# JP-LED.net
KiCad netlist of a schematic drawn in Altium Designer
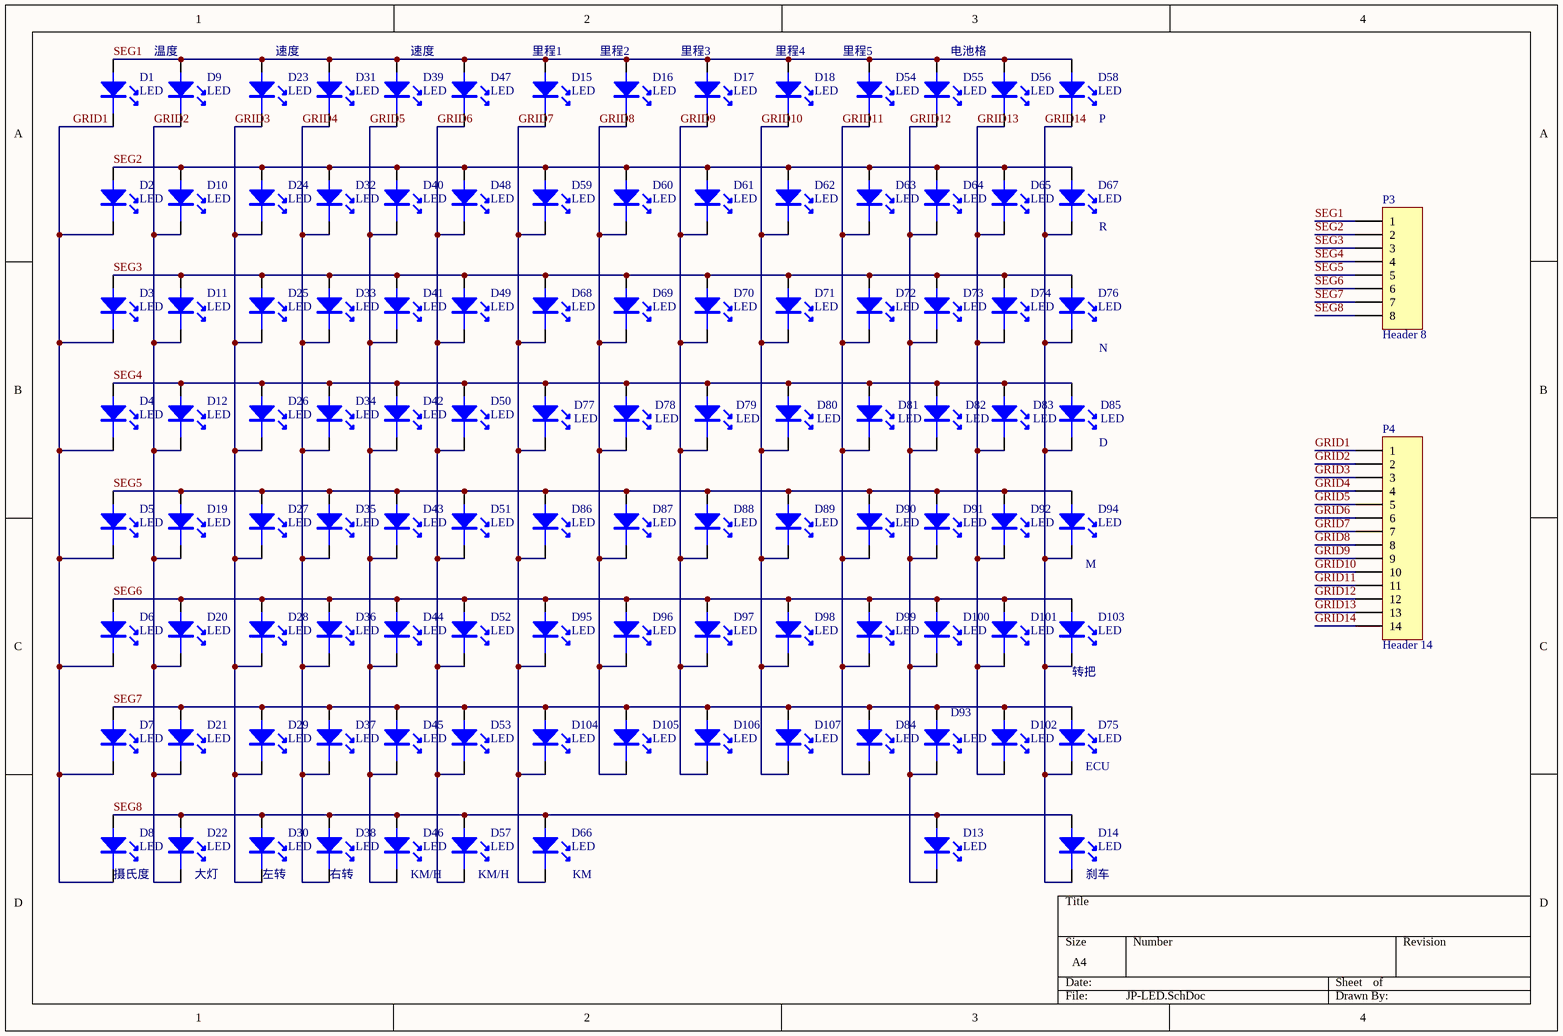
[diagram p0: JP-LED.SchDoc]

(export (version "E")
  (design (tool "Eeschema 10.0.6"))
  (components
    (comp (ref "D1") (value "LED") (footprint "0603-LED") (libsource (lib "dsp") (part "LED")))
    (comp (ref "D2") (value "LED") (footprint "0603-LED") (libsource (lib "dsp") (part "LED")))
    (comp (ref "D3") (value "LED") (footprint "0603-LED") (libsource (lib "dsp") (part "LED")))
    (comp (ref "D4") (value "LED") (footprint "0603-LED") (libsource (lib "dsp") (part "LED")))
    (comp (ref "D5") (value "LED") (footprint "0603-LED") (libsource (lib "dsp") (part "LED")))
    (comp (ref "D6") (value "LED") (footprint "0603-LED") (libsource (lib "dsp") (part "LED")))
    (comp (ref "D7") (value "LED") (footprint "0603-LED") (libsource (lib "dsp") (part "LED")))
    (comp (ref "D8") (value "LED") (footprint "0603-LED") (libsource (lib "dsp") (part "LED")))
    (comp (ref "D9") (value "LED") (footprint "0603-LED") (libsource (lib "dsp") (part "LED")))
    (comp (ref "D10") (value "LED") (footprint "0603-LED") (libsource (lib "dsp") (part "LED")))
    (comp (ref "D11") (value "LED") (footprint "0603-LED") (libsource (lib "dsp") (part "LED")))
    (comp (ref "D12") (value "LED") (footprint "0603-LED") (libsource (lib "dsp") (part "LED")))
    (comp (ref "D13") (value "LED") (footprint "0603-LED") (libsource (lib "dsp") (part "LED")))
    (comp (ref "D14") (value "LED") (footprint "0603-LED") (libsource (lib "dsp") (part "LED")))
    (comp (ref "D15") (value "LED") (footprint "0603-LED") (libsource (lib "dsp") (part "LED")))
    (comp (ref "D16") (value "LED") (footprint "0603-LED") (libsource (lib "dsp") (part "LED")))
    (comp (ref "D17") (value "LED") (footprint "0603-LED") (libsource (lib "dsp") (part "LED")))
    (comp (ref "D18") (value "LED") (footprint "0603-LED") (libsource (lib "dsp") (part "LED")))
    (comp (ref "D19") (value "LED") (footprint "0603-LED") (libsource (lib "dsp") (part "LED")))
    (comp (ref "D20") (value "LED") (footprint "0603-LED") (libsource (lib "dsp") (part "LED")))
    (comp (ref "D21") (value "LED") (footprint "0603-LED") (libsource (lib "dsp") (part "LED")))
    (comp (ref "D22") (value "LED") (footprint "0603-LED") (libsource (lib "dsp") (part "LED")))
    (comp (ref "D23") (value "LED") (footprint "0603-LED") (libsource (lib "dsp") (part "LED")))
    (comp (ref "D24") (value "LED") (footprint "0603-LED") (libsource (lib "dsp") (part "LED")))
    (comp (ref "D25") (value "LED") (footprint "0603-LED") (libsource (lib "dsp") (part "LED")))
    (comp (ref "D26") (value "LED") (footprint "0603-LED") (libsource (lib "dsp") (part "LED")))
    (comp (ref "D27") (value "LED") (footprint "0603-LED") (libsource (lib "dsp") (part "LED")))
    (comp (ref "D28") (value "LED") (footprint "0603-LED") (libsource (lib "dsp") (part "LED")))
    (comp (ref "D29") (value "LED") (footprint "0603-LED") (libsource (lib "dsp") (part "LED")))
    (comp (ref "D30") (value "LED") (footprint "0603-LED") (libsource (lib "dsp") (part "LED")))
    (comp (ref "D31") (value "LED") (footprint "0603-LED") (libsource (lib "dsp") (part "LED")))
    (comp (ref "D32") (value "LED") (footprint "0603-LED") (libsource (lib "dsp") (part "LED")))
    (comp (ref "D33") (value "LED") (footprint "0603-LED") (libsource (lib "dsp") (part "LED")))
    (comp (ref "D34") (value "LED") (footprint "0603-LED") (libsource (lib "dsp") (part "LED")))
    (comp (ref "D35") (value "LED") (footprint "0603-LED") (libsource (lib "dsp") (part "LED")))
    (comp (ref "D36") (value "LED") (footprint "0603-LED") (libsource (lib "dsp") (part "LED")))
    (comp (ref "D37") (value "LED") (footprint "0603-LED") (libsource (lib "dsp") (part "LED")))
    (comp (ref "D38") (value "LED") (footprint "0603-LED") (libsource (lib "dsp") (part "LED")))
    (comp (ref "D39") (value "LED") (footprint "0603-LED") (libsource (lib "dsp") (part "LED")))
    (comp (ref "D40") (value "LED") (footprint "0603-LED") (libsource (lib "dsp") (part "LED")))
    (comp (ref "D41") (value "LED") (footprint "0603-LED") (libsource (lib "dsp") (part "LED")))
    (comp (ref "D42") (value "LED") (footprint "0603-LED") (libsource (lib "dsp") (part "LED")))
    (comp (ref "D43") (value "LED") (footprint "0603-LED") (libsource (lib "dsp") (part "LED")))
    (comp (ref "D44") (value "LED") (footprint "0603-LED") (libsource (lib "dsp") (part "LED")))
    (comp (ref "D45") (value "LED") (footprint "0603-LED") (libsource (lib "dsp") (part "LED")))
    (comp (ref "D46") (value "LED") (footprint "0603-LED") (libsource (lib "dsp") (part "LED")))
    (comp (ref "D47") (value "LED") (footprint "0603-LED") (libsource (lib "dsp") (part "LED")))
    (comp (ref "D48") (value "LED") (footprint "0603-LED") (libsource (lib "dsp") (part "LED")))
    (comp (ref "D49") (value "LED") (footprint "0603-LED") (libsource (lib "dsp") (part "LED")))
    (comp (ref "D50") (value "LED") (footprint "0603-LED") (libsource (lib "dsp") (part "LED")))
    (comp (ref "D51") (value "LED") (footprint "0603-LED") (libsource (lib "dsp") (part "LED")))
    (comp (ref "D52") (value "LED") (footprint "0603-LED") (libsource (lib "dsp") (part "LED")))
    (comp (ref "D53") (value "LED") (footprint "0603-LED") (libsource (lib "dsp") (part "LED")))
    (comp (ref "D54") (value "LED") (footprint "0603-LED") (libsource (lib "dsp") (part "LED")))
    (comp (ref "D55") (value "LED") (footprint "0603-LED") (libsource (lib "dsp") (part "LED")))
    (comp (ref "D56") (value "LED") (footprint "0603-LED") (libsource (lib "dsp") (part "LED")))
    (comp (ref "D57") (value "LED") (footprint "0603-LED") (libsource (lib "dsp") (part "LED")))
    (comp (ref "D58") (value "LED") (footprint "0603-LED") (libsource (lib "dsp") (part "LED")))
    (comp (ref "D59") (value "LED") (footprint "0603-LED") (libsource (lib "dsp") (part "LED")))
    (comp (ref "D60") (value "LED") (footprint "0603-LED") (libsource (lib "dsp") (part "LED")))
    (comp (ref "D61") (value "LED") (footprint "0603-LED") (libsource (lib "dsp") (part "LED")))
    (comp (ref "D62") (value "LED") (footprint "0603-LED") (libsource (lib "dsp") (part "LED")))
    (comp (ref "D63") (value "LED") (footprint "0603-LED") (libsource (lib "dsp") (part "LED")))
    (comp (ref "D64") (value "LED") (footprint "0603-LED") (libsource (lib "dsp") (part "LED")))
    (comp (ref "D65") (value "LED") (footprint "0603-LED") (libsource (lib "dsp") (part "LED")))
    (comp (ref "D66") (value "LED") (footprint "0603-LED") (libsource (lib "dsp") (part "LED")))
    (comp (ref "D67") (value "LED") (footprint "0603-LED") (libsource (lib "dsp") (part "LED")))
    (comp (ref "D68") (value "LED") (footprint "0603-LED") (libsource (lib "dsp") (part "LED")))
    (comp (ref "D69") (value "LED") (footprint "0603-LED") (libsource (lib "dsp") (part "LED")))
    (comp (ref "D70") (value "LED") (footprint "0603-LED") (libsource (lib "dsp") (part "LED")))
    (comp (ref "D71") (value "LED") (footprint "0603-LED") (libsource (lib "dsp") (part "LED")))
    (comp (ref "D72") (value "LED") (footprint "0603-LED") (libsource (lib "dsp") (part "LED")))
    (comp (ref "D73") (value "LED") (footprint "0603-LED") (libsource (lib "dsp") (part "LED")))
    (comp (ref "D74") (value "LED") (footprint "0603-LED") (libsource (lib "dsp") (part "LED")))
    (comp (ref "D75") (value "LED") (footprint "0603-LED") (libsource (lib "dsp") (part "LED")))
    (comp (ref "D76") (value "LED") (footprint "0603-LED") (libsource (lib "dsp") (part "LED")))
    (comp (ref "D77") (value "LED") (footprint "0603-LED") (libsource (lib "dsp") (part "LED")))
    (comp (ref "D78") (value "LED") (footprint "0603-LED") (libsource (lib "dsp") (part "LED")))
    (comp (ref "D79") (value "LED") (footprint "0603-LED") (libsource (lib "dsp") (part "LED")))
    (comp (ref "D80") (value "LED") (footprint "0603-LED") (libsource (lib "dsp") (part "LED")))
    (comp (ref "D81") (value "LED") (footprint "0603-LED") (libsource (lib "dsp") (part "LED")))
    (comp (ref "D82") (value "LED") (footprint "0603-LED") (libsource (lib "dsp") (part "LED")))
    (comp (ref "D83") (value "LED") (footprint "0603-LED") (libsource (lib "dsp") (part "LED")))
    (comp (ref "D84") (value "LED") (footprint "0603-LED") (libsource (lib "dsp") (part "LED")))
    (comp (ref "D85") (value "LED") (footprint "0603-LED") (libsource (lib "dsp") (part "LED")))
    (comp (ref "D86") (value "LED") (footprint "0603-LED") (libsource (lib "dsp") (part "LED")))
    (comp (ref "D87") (value "LED") (footprint "0603-LED") (libsource (lib "dsp") (part "LED")))
    (comp (ref "D88") (value "LED") (footprint "0603-LED") (libsource (lib "dsp") (part "LED")))
    (comp (ref "D89") (value "LED") (footprint "0603-LED") (libsource (lib "dsp") (part "LED")))
    (comp (ref "D90") (value "LED") (footprint "0603-LED") (libsource (lib "dsp") (part "LED")))
    (comp (ref "D91") (value "LED") (footprint "0603-LED") (libsource (lib "dsp") (part "LED")))
    (comp (ref "D92") (value "LED") (footprint "0603-LED") (libsource (lib "dsp") (part "LED")))
    (comp (ref "D93") (value "LED") (footprint "0603-LED") (libsource (lib "dsp") (part "LED")))
    (comp (ref "D94") (value "LED") (footprint "0603-LED") (libsource (lib "dsp") (part "LED")))
    (comp (ref "D95") (value "LED") (footprint "0603-LED") (libsource (lib "dsp") (part "LED")))
    (comp (ref "D96") (value "LED") (footprint "0603-LED") (libsource (lib "dsp") (part "LED")))
    (comp (ref "D97") (value "LED") (footprint "0603-LED") (libsource (lib "dsp") (part "LED")))
    (comp (ref "D98") (value "LED") (footprint "0603-LED") (libsource (lib "dsp") (part "LED")))
    (comp (ref "D99") (value "LED") (footprint "0603-LED") (libsource (lib "dsp") (part "LED")))
    (comp (ref "D100") (value "LED") (footprint "0603-LED") (libsource (lib "dsp") (part "LED")))
    (comp (ref "D101") (value "LED") (footprint "0603-LED") (libsource (lib "dsp") (part "LED")))
    (comp (ref "D102") (value "LED") (footprint "0603-LED") (libsource (lib "dsp") (part "LED")))
    (comp (ref "D103") (value "LED") (footprint "0603-LED") (libsource (lib "dsp") (part "LED")))
    (comp (ref "D104") (value "LED") (footprint "0603-LED") (libsource (lib "dsp") (part "LED")))
    (comp (ref "D105") (value "LED") (footprint "0603-LED") (libsource (lib "dsp") (part "LED")))
    (comp (ref "D106") (value "LED") (footprint "0603-LED") (libsource (lib "dsp") (part "LED")))
    (comp (ref "D107") (value "LED") (footprint "0603-LED") (libsource (lib "dsp") (part "LED")))
    (comp (ref "P3")
      (value "Header 8")
      (footprint "HDR1X8")
      (description "Header, 8-Pin")
      (fields (field (name "PUBLISHER") "Altium Limited"))
      (libsource (lib "Miscellaneous Connectors") (part "Header 8"))
    )
    (comp (ref "P4")
      (value "Header 14")
      (footprint "SIP14")
      (description "Header, 14-Pin")
      (fields (field (name "PUBLISHER") "Altium Limited"))
      (libsource (lib "9040") (part "Header 14"))
    )
  )
  (nets
    (net (code "1") (name "/GRID1") (class "Default")
      (node (ref "D1") (pin "2") (pinfunction "2_2") (pintype "passive"))
      (node (ref "D2") (pin "2") (pinfunction "2_2") (pintype "passive"))
      (node (ref "D3") (pin "2") (pinfunction "2_2") (pintype "passive"))
      (node (ref "D4") (pin "2") (pinfunction "2_2") (pintype "passive"))
      (node (ref "D5") (pin "2") (pinfunction "2_2") (pintype "passive"))
      (node (ref "D6") (pin "2") (pinfunction "2_2") (pintype "passive"))
      (node (ref "D7") (pin "2") (pinfunction "2_2") (pintype "passive"))
      (node (ref "D8") (pin "2") (pinfunction "2_2") (pintype "passive"))
      (node (ref "P4") (pin "1") (pinfunction "1_1") (pintype "passive"))
    )
    (net (code "2") (name "/GRID2") (class "Default")
      (node (ref "D10") (pin "2") (pinfunction "2_2") (pintype "passive"))
      (node (ref "D11") (pin "2") (pinfunction "2_2") (pintype "passive"))
      (node (ref "D12") (pin "2") (pinfunction "2_2") (pintype "passive"))
      (node (ref "D19") (pin "2") (pinfunction "2_2") (pintype "passive"))
      (node (ref "D20") (pin "2") (pinfunction "2_2") (pintype "passive"))
      (node (ref "D21") (pin "2") (pinfunction "2_2") (pintype "passive"))
      (node (ref "D22") (pin "2") (pinfunction "2_2") (pintype "passive"))
      (node (ref "D9") (pin "2") (pinfunction "2_2") (pintype "passive"))
      (node (ref "P4") (pin "2") (pinfunction "2_2") (pintype "passive"))
    )
    (net (code "3") (name "/GRID3") (class "Default")
      (node (ref "D23") (pin "2") (pinfunction "2_2") (pintype "passive"))
      (node (ref "D24") (pin "2") (pinfunction "2_2") (pintype "passive"))
      (node (ref "D25") (pin "2") (pinfunction "2_2") (pintype "passive"))
      (node (ref "D26") (pin "2") (pinfunction "2_2") (pintype "passive"))
      (node (ref "D27") (pin "2") (pinfunction "2_2") (pintype "passive"))
      (node (ref "D28") (pin "2") (pinfunction "2_2") (pintype "passive"))
      (node (ref "D29") (pin "2") (pinfunction "2_2") (pintype "passive"))
      (node (ref "D30") (pin "2") (pinfunction "2_2") (pintype "passive"))
      (node (ref "P4") (pin "3") (pinfunction "3_3") (pintype "passive"))
    )
    (net (code "4") (name "/GRID4") (class "Default")
      (node (ref "D31") (pin "2") (pinfunction "2_2") (pintype "passive"))
      (node (ref "D32") (pin "2") (pinfunction "2_2") (pintype "passive"))
      (node (ref "D33") (pin "2") (pinfunction "2_2") (pintype "passive"))
      (node (ref "D34") (pin "2") (pinfunction "2_2") (pintype "passive"))
      (node (ref "D35") (pin "2") (pinfunction "2_2") (pintype "passive"))
      (node (ref "D36") (pin "2") (pinfunction "2_2") (pintype "passive"))
      (node (ref "D37") (pin "2") (pinfunction "2_2") (pintype "passive"))
      (node (ref "D38") (pin "2") (pinfunction "2_2") (pintype "passive"))
      (node (ref "P4") (pin "4") (pinfunction "4_4") (pintype "passive"))
    )
    (net (code "5") (name "/GRID5") (class "Default")
      (node (ref "D39") (pin "2") (pinfunction "2_2") (pintype "passive"))
      (node (ref "D40") (pin "2") (pinfunction "2_2") (pintype "passive"))
      (node (ref "D41") (pin "2") (pinfunction "2_2") (pintype "passive"))
      (node (ref "D42") (pin "2") (pinfunction "2_2") (pintype "passive"))
      (node (ref "D43") (pin "2") (pinfunction "2_2") (pintype "passive"))
      (node (ref "D44") (pin "2") (pinfunction "2_2") (pintype "passive"))
      (node (ref "D45") (pin "2") (pinfunction "2_2") (pintype "passive"))
      (node (ref "D46") (pin "2") (pinfunction "2_2") (pintype "passive"))
      (node (ref "P4") (pin "5") (pinfunction "5_5") (pintype "passive"))
    )
    (net (code "6") (name "/GRID6") (class "Default")
      (node (ref "D47") (pin "2") (pinfunction "2_2") (pintype "passive"))
      (node (ref "D48") (pin "2") (pinfunction "2_2") (pintype "passive"))
      (node (ref "D49") (pin "2") (pinfunction "2_2") (pintype "passive"))
      (node (ref "D50") (pin "2") (pinfunction "2_2") (pintype "passive"))
      (node (ref "D51") (pin "2") (pinfunction "2_2") (pintype "passive"))
      (node (ref "D52") (pin "2") (pinfunction "2_2") (pintype "passive"))
      (node (ref "D53") (pin "2") (pinfunction "2_2") (pintype "passive"))
      (node (ref "D57") (pin "2") (pinfunction "2_2") (pintype "passive"))
      (node (ref "P4") (pin "6") (pinfunction "6_6") (pintype "passive"))
    )
    (net (code "7") (name "/GRID7") (class "Default")
      (node (ref "D104") (pin "2") (pinfunction "2_2") (pintype "passive"))
      (node (ref "D15") (pin "2") (pinfunction "2_2") (pintype "passive"))
      (node (ref "D59") (pin "2") (pinfunction "2_2") (pintype "passive"))
      (node (ref "D66") (pin "2") (pinfunction "2_2") (pintype "passive"))
      (node (ref "D68") (pin "2") (pinfunction "2_2") (pintype "passive"))
      (node (ref "D77") (pin "2") (pinfunction "2_2") (pintype "passive"))
      (node (ref "D86") (pin "2") (pinfunction "2_2") (pintype "passive"))
      (node (ref "D95") (pin "2") (pinfunction "2_2") (pintype "passive"))
      (node (ref "P4") (pin "7") (pinfunction "7_7") (pintype "passive"))
    )
    (net (code "8") (name "/GRID8") (class "Default")
      (node (ref "D105") (pin "2") (pinfunction "2_2") (pintype "passive"))
      (node (ref "D16") (pin "2") (pinfunction "2_2") (pintype "passive"))
      (node (ref "D60") (pin "2") (pinfunction "2_2") (pintype "passive"))
      (node (ref "D69") (pin "2") (pinfunction "2_2") (pintype "passive"))
      (node (ref "D78") (pin "2") (pinfunction "2_2") (pintype "passive"))
      (node (ref "D87") (pin "2") (pinfunction "2_2") (pintype "passive"))
      (node (ref "D96") (pin "2") (pinfunction "2_2") (pintype "passive"))
      (node (ref "P4") (pin "8") (pinfunction "8_8") (pintype "passive"))
    )
    (net (code "9") (name "/GRID9") (class "Default")
      (node (ref "D106") (pin "2") (pinfunction "2_2") (pintype "passive"))
      (node (ref "D17") (pin "2") (pinfunction "2_2") (pintype "passive"))
      (node (ref "D61") (pin "2") (pinfunction "2_2") (pintype "passive"))
      (node (ref "D70") (pin "2") (pinfunction "2_2") (pintype "passive"))
      (node (ref "D79") (pin "2") (pinfunction "2_2") (pintype "passive"))
      (node (ref "D88") (pin "2") (pinfunction "2_2") (pintype "passive"))
      (node (ref "D97") (pin "2") (pinfunction "2_2") (pintype "passive"))
      (node (ref "P4") (pin "9") (pinfunction "9_9") (pintype "passive"))
    )
    (net (code "10") (name "/GRID10") (class "Default")
      (node (ref "D107") (pin "2") (pinfunction "2_2") (pintype "passive"))
      (node (ref "D18") (pin "2") (pinfunction "2_2") (pintype "passive"))
      (node (ref "D62") (pin "2") (pinfunction "2_2") (pintype "passive"))
      (node (ref "D71") (pin "2") (pinfunction "2_2") (pintype "passive"))
      (node (ref "D80") (pin "2") (pinfunction "2_2") (pintype "passive"))
      (node (ref "D89") (pin "2") (pinfunction "2_2") (pintype "passive"))
      (node (ref "D98") (pin "2") (pinfunction "2_2") (pintype "passive"))
      (node (ref "P4") (pin "10") (pinfunction "10_10") (pintype "passive"))
    )
    (net (code "11") (name "/GRID11") (class "Default")
      (node (ref "D54") (pin "2") (pinfunction "2_2") (pintype "passive"))
      (node (ref "D63") (pin "2") (pinfunction "2_2") (pintype "passive"))
      (node (ref "D72") (pin "2") (pinfunction "2_2") (pintype "passive"))
      (node (ref "D81") (pin "2") (pinfunction "2_2") (pintype "passive"))
      (node (ref "D84") (pin "2") (pinfunction "2_2") (pintype "passive"))
      (node (ref "D90") (pin "2") (pinfunction "2_2") (pintype "passive"))
      (node (ref "D99") (pin "2") (pinfunction "2_2") (pintype "passive"))
      (node (ref "P4") (pin "11") (pinfunction "11_11") (pintype "passive"))
    )
    (net (code "12") (name "/GRID12") (class "Default")
      (node (ref "D100") (pin "2") (pinfunction "2_2") (pintype "passive"))
      (node (ref "D13") (pin "2") (pinfunction "2_2") (pintype "passive"))
      (node (ref "D55") (pin "2") (pinfunction "2_2") (pintype "passive"))
      (node (ref "D64") (pin "2") (pinfunction "2_2") (pintype "passive"))
      (node (ref "D73") (pin "2") (pinfunction "2_2") (pintype "passive"))
      (node (ref "D82") (pin "2") (pinfunction "2_2") (pintype "passive"))
      (node (ref "D91") (pin "2") (pinfunction "2_2") (pintype "passive"))
      (node (ref "D93") (pin "2") (pinfunction "2_2") (pintype "passive"))
      (node (ref "P4") (pin "12") (pinfunction "12_12") (pintype "passive"))
    )
    (net (code "13") (name "/GRID13") (class "Default")
      (node (ref "D101") (pin "2") (pinfunction "2_2") (pintype "passive"))
      (node (ref "D102") (pin "2") (pinfunction "2_2") (pintype "passive"))
      (node (ref "D56") (pin "2") (pinfunction "2_2") (pintype "passive"))
      (node (ref "D65") (pin "2") (pinfunction "2_2") (pintype "passive"))
      (node (ref "D74") (pin "2") (pinfunction "2_2") (pintype "passive"))
      (node (ref "D83") (pin "2") (pinfunction "2_2") (pintype "passive"))
      (node (ref "D92") (pin "2") (pinfunction "2_2") (pintype "passive"))
      (node (ref "P4") (pin "13") (pinfunction "13_13") (pintype "passive"))
    )
    (net (code "14") (name "/GRID14") (class "Default")
      (node (ref "D103") (pin "2") (pinfunction "2_2") (pintype "passive"))
      (node (ref "D14") (pin "2") (pinfunction "2_2") (pintype "passive"))
      (node (ref "D58") (pin "2") (pinfunction "2_2") (pintype "passive"))
      (node (ref "D67") (pin "2") (pinfunction "2_2") (pintype "passive"))
      (node (ref "D75") (pin "2") (pinfunction "2_2") (pintype "passive"))
      (node (ref "D76") (pin "2") (pinfunction "2_2") (pintype "passive"))
      (node (ref "D85") (pin "2") (pinfunction "2_2") (pintype "passive"))
      (node (ref "D94") (pin "2") (pinfunction "2_2") (pintype "passive"))
      (node (ref "P4") (pin "14") (pinfunction "14_14") (pintype "passive"))
    )
    (net (code "15") (name "/SEG1") (class "Default")
      (node (ref "D1") (pin "1") (pinfunction "1_1") (pintype "passive"))
      (node (ref "D15") (pin "1") (pinfunction "1_1") (pintype "passive"))
      (node (ref "D16") (pin "1") (pinfunction "1_1") (pintype "passive"))
      (node (ref "D17") (pin "1") (pinfunction "1_1") (pintype "passive"))
      (node (ref "D18") (pin "1") (pinfunction "1_1") (pintype "passive"))
      (node (ref "D23") (pin "1") (pinfunction "1_1") (pintype "passive"))
      (node (ref "D31") (pin "1") (pinfunction "1_1") (pintype "passive"))
      (node (ref "D39") (pin "1") (pinfunction "1_1") (pintype "passive"))
      (node (ref "D47") (pin "1") (pinfunction "1_1") (pintype "passive"))
      (node (ref "D54") (pin "1") (pinfunction "1_1") (pintype "passive"))
      (node (ref "D55") (pin "1") (pinfunction "1_1") (pintype "passive"))
      (node (ref "D56") (pin "1") (pinfunction "1_1") (pintype "passive"))
      (node (ref "D58") (pin "1") (pinfunction "1_1") (pintype "passive"))
      (node (ref "D9") (pin "1") (pinfunction "1_1") (pintype "passive"))
      (node (ref "P3") (pin "1") (pinfunction "1_1") (pintype "passive"))
    )
    (net (code "16") (name "/SEG2") (class "Default")
      (node (ref "D10") (pin "1") (pinfunction "1_1") (pintype "passive"))
      (node (ref "D2") (pin "1") (pinfunction "1_1") (pintype "passive"))
      (node (ref "D24") (pin "1") (pinfunction "1_1") (pintype "passive"))
      (node (ref "D32") (pin "1") (pinfunction "1_1") (pintype "passive"))
      (node (ref "D40") (pin "1") (pinfunction "1_1") (pintype "passive"))
      (node (ref "D48") (pin "1") (pinfunction "1_1") (pintype "passive"))
      (node (ref "D59") (pin "1") (pinfunction "1_1") (pintype "passive"))
      (node (ref "D60") (pin "1") (pinfunction "1_1") (pintype "passive"))
      (node (ref "D61") (pin "1") (pinfunction "1_1") (pintype "passive"))
      (node (ref "D62") (pin "1") (pinfunction "1_1") (pintype "passive"))
      (node (ref "D63") (pin "1") (pinfunction "1_1") (pintype "passive"))
      (node (ref "D64") (pin "1") (pinfunction "1_1") (pintype "passive"))
      (node (ref "D65") (pin "1") (pinfunction "1_1") (pintype "passive"))
      (node (ref "D67") (pin "1") (pinfunction "1_1") (pintype "passive"))
      (node (ref "P3") (pin "2") (pinfunction "2_2") (pintype "passive"))
    )
    (net (code "17") (name "/SEG3") (class "Default")
      (node (ref "D11") (pin "1") (pinfunction "1_1") (pintype "passive"))
      (node (ref "D25") (pin "1") (pinfunction "1_1") (pintype "passive"))
      (node (ref "D3") (pin "1") (pinfunction "1_1") (pintype "passive"))
      (node (ref "D33") (pin "1") (pinfunction "1_1") (pintype "passive"))
      (node (ref "D41") (pin "1") (pinfunction "1_1") (pintype "passive"))
      (node (ref "D49") (pin "1") (pinfunction "1_1") (pintype "passive"))
      (node (ref "D68") (pin "1") (pinfunction "1_1") (pintype "passive"))
      (node (ref "D69") (pin "1") (pinfunction "1_1") (pintype "passive"))
      (node (ref "D70") (pin "1") (pinfunction "1_1") (pintype "passive"))
      (node (ref "D71") (pin "1") (pinfunction "1_1") (pintype "passive"))
      (node (ref "D72") (pin "1") (pinfunction "1_1") (pintype "passive"))
      (node (ref "D73") (pin "1") (pinfunction "1_1") (pintype "passive"))
      (node (ref "D74") (pin "1") (pinfunction "1_1") (pintype "passive"))
      (node (ref "D76") (pin "1") (pinfunction "1_1") (pintype "passive"))
      (node (ref "P3") (pin "3") (pinfunction "3_3") (pintype "passive"))
    )
    (net (code "18") (name "/SEG4") (class "Default")
      (node (ref "D12") (pin "1") (pinfunction "1_1") (pintype "passive"))
      (node (ref "D26") (pin "1") (pinfunction "1_1") (pintype "passive"))
      (node (ref "D34") (pin "1") (pinfunction "1_1") (pintype "passive"))
      (node (ref "D4") (pin "1") (pinfunction "1_1") (pintype "passive"))
      (node (ref "D42") (pin "1") (pinfunction "1_1") (pintype "passive"))
      (node (ref "D50") (pin "1") (pinfunction "1_1") (pintype "passive"))
      (node (ref "D77") (pin "1") (pinfunction "1_1") (pintype "passive"))
      (node (ref "D78") (pin "1") (pinfunction "1_1") (pintype "passive"))
      (node (ref "D79") (pin "1") (pinfunction "1_1") (pintype "passive"))
      (node (ref "D80") (pin "1") (pinfunction "1_1") (pintype "passive"))
      (node (ref "D81") (pin "1") (pinfunction "1_1") (pintype "passive"))
      (node (ref "D82") (pin "1") (pinfunction "1_1") (pintype "passive"))
      (node (ref "D83") (pin "1") (pinfunction "1_1") (pintype "passive"))
      (node (ref "D85") (pin "1") (pinfunction "1_1") (pintype "passive"))
      (node (ref "P3") (pin "4") (pinfunction "4_4") (pintype "passive"))
    )
    (net (code "19") (name "/SEG5") (class "Default")
      (node (ref "D19") (pin "1") (pinfunction "1_1") (pintype "passive"))
      (node (ref "D27") (pin "1") (pinfunction "1_1") (pintype "passive"))
      (node (ref "D35") (pin "1") (pinfunction "1_1") (pintype "passive"))
      (node (ref "D43") (pin "1") (pinfunction "1_1") (pintype "passive"))
      (node (ref "D5") (pin "1") (pinfunction "1_1") (pintype "passive"))
      (node (ref "D51") (pin "1") (pinfunction "1_1") (pintype "passive"))
      (node (ref "D86") (pin "1") (pinfunction "1_1") (pintype "passive"))
      (node (ref "D87") (pin "1") (pinfunction "1_1") (pintype "passive"))
      (node (ref "D88") (pin "1") (pinfunction "1_1") (pintype "passive"))
      (node (ref "D89") (pin "1") (pinfunction "1_1") (pintype "passive"))
      (node (ref "D90") (pin "1") (pinfunction "1_1") (pintype "passive"))
      (node (ref "D91") (pin "1") (pinfunction "1_1") (pintype "passive"))
      (node (ref "D92") (pin "1") (pinfunction "1_1") (pintype "passive"))
      (node (ref "D94") (pin "1") (pinfunction "1_1") (pintype "passive"))
      (node (ref "P3") (pin "5") (pinfunction "5_5") (pintype "passive"))
    )
    (net (code "20") (name "/SEG6") (class "Default")
      (node (ref "D100") (pin "1") (pinfunction "1_1") (pintype "passive"))
      (node (ref "D101") (pin "1") (pinfunction "1_1") (pintype "passive"))
      (node (ref "D103") (pin "1") (pinfunction "1_1") (pintype "passive"))
      (node (ref "D20") (pin "1") (pinfunction "1_1") (pintype "passive"))
      (node (ref "D28") (pin "1") (pinfunction "1_1") (pintype "passive"))
      (node (ref "D36") (pin "1") (pinfunction "1_1") (pintype "passive"))
      (node (ref "D44") (pin "1") (pinfunction "1_1") (pintype "passive"))
      (node (ref "D52") (pin "1") (pinfunction "1_1") (pintype "passive"))
      (node (ref "D6") (pin "1") (pinfunction "1_1") (pintype "passive"))
      (node (ref "D95") (pin "1") (pinfunction "1_1") (pintype "passive"))
      (node (ref "D96") (pin "1") (pinfunction "1_1") (pintype "passive"))
      (node (ref "D97") (pin "1") (pinfunction "1_1") (pintype "passive"))
      (node (ref "D98") (pin "1") (pinfunction "1_1") (pintype "passive"))
      (node (ref "D99") (pin "1") (pinfunction "1_1") (pintype "passive"))
      (node (ref "P3") (pin "6") (pinfunction "6_6") (pintype "passive"))
    )
    (net (code "21") (name "/SEG7") (class "Default")
      (node (ref "D102") (pin "1") (pinfunction "1_1") (pintype "passive"))
      (node (ref "D104") (pin "1") (pinfunction "1_1") (pintype "passive"))
      (node (ref "D105") (pin "1") (pinfunction "1_1") (pintype "passive"))
      (node (ref "D106") (pin "1") (pinfunction "1_1") (pintype "passive"))
      (node (ref "D107") (pin "1") (pinfunction "1_1") (pintype "passive"))
      (node (ref "D21") (pin "1") (pinfunction "1_1") (pintype "passive"))
      (node (ref "D29") (pin "1") (pinfunction "1_1") (pintype "passive"))
      (node (ref "D37") (pin "1") (pinfunction "1_1") (pintype "passive"))
      (node (ref "D45") (pin "1") (pinfunction "1_1") (pintype "passive"))
      (node (ref "D53") (pin "1") (pinfunction "1_1") (pintype "passive"))
      (node (ref "D7") (pin "1") (pinfunction "1_1") (pintype "passive"))
      (node (ref "D75") (pin "1") (pinfunction "1_1") (pintype "passive"))
      (node (ref "D84") (pin "1") (pinfunction "1_1") (pintype "passive"))
      (node (ref "D93") (pin "1") (pinfunction "1_1") (pintype "passive"))
      (node (ref "P3") (pin "7") (pinfunction "7_7") (pintype "passive"))
    )
    (net (code "22") (name "/SEG8") (class "Default")
      (node (ref "D13") (pin "1") (pinfunction "1_1") (pintype "passive"))
      (node (ref "D14") (pin "1") (pinfunction "1_1") (pintype "passive"))
      (node (ref "D22") (pin "1") (pinfunction "1_1") (pintype "passive"))
      (node (ref "D30") (pin "1") (pinfunction "1_1") (pintype "passive"))
      (node (ref "D38") (pin "1") (pinfunction "1_1") (pintype "passive"))
      (node (ref "D46") (pin "1") (pinfunction "1_1") (pintype "passive"))
      (node (ref "D57") (pin "1") (pinfunction "1_1") (pintype "passive"))
      (node (ref "D66") (pin "1") (pinfunction "1_1") (pintype "passive"))
      (node (ref "D8") (pin "1") (pinfunction "1_1") (pintype "passive"))
      (node (ref "P3") (pin "8") (pinfunction "8_8") (pintype "passive"))
    )
  )
)
